# ICM40609.net
KiCad netlist of a schematic drawn in Altium Designer
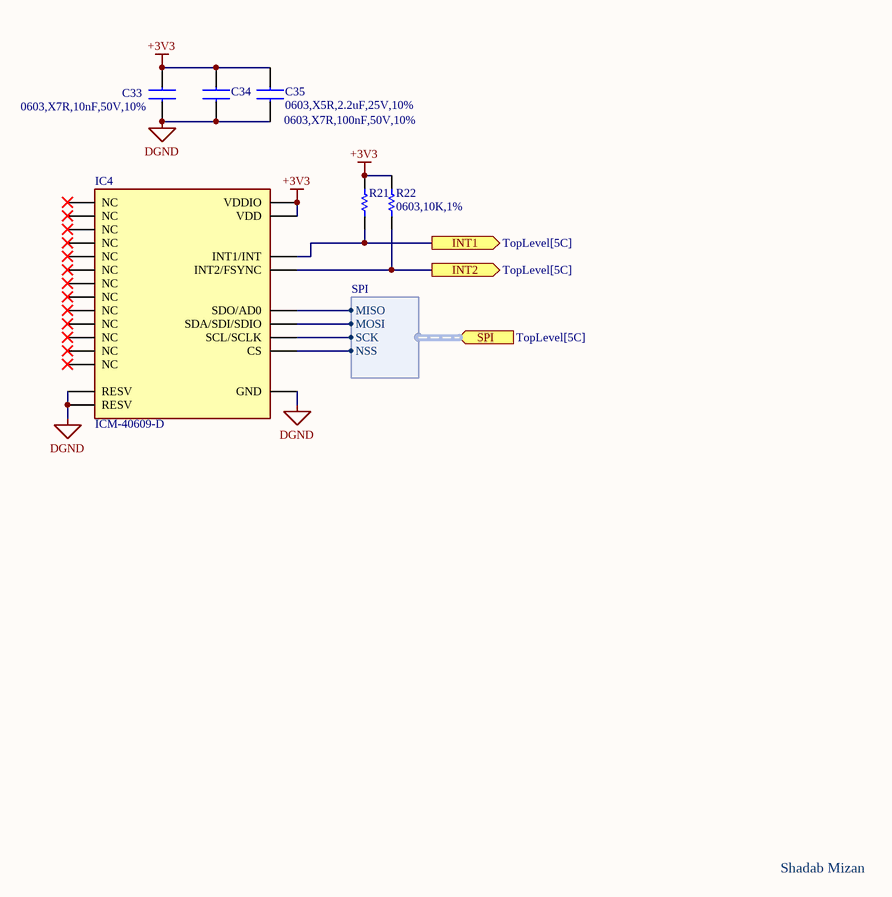
[diagram p0: ICM40609.SchDoc]

(export (version "E")
  (design (tool "Eeschema 10.0.6"))
  (components
    (comp (ref "C33")
      (value "0603,X7R,10nF,50V,10%")
      (footprint "CAPC1608X90N")
      (description "10nF ±10% 50V Ceramic Capacitor X7R 0603")
      (fields (field (name "LCSC PART #") "C57112") (field (name "MANU PART #") "0603B103K500NT"))
      (libsource (lib "flight-controller") (part "0603B103K500NT"))
    )
    (comp (ref "C34")
      (value "0603,X7R,100nF,50V,10%")
      (footprint "CAPC1608X90N")
      (description "50V 100nF X7R ±10% 0603 Multilayer Ceramic Capacitors MLCC - SMD/SMT ROHS")
      (fields (field (name "LCSC PART #") "C14663") (field (name "MANU PART #") "CC0603KRX7R9BB104"))
      (libsource (lib "flight-controller") (part "CC0603KRX7R9BB104"))
    )
    (comp (ref "C35")
      (value "0603,X5R,2.2uF,25V,10%")
      (footprint "CAPC1608X90N")
      (description "2.2 µF ±10% 25V Ceramic Capacitor X5R 0603 (1608 Metric)")
      (fields (field (name "MANU PART #") "CL10A225KO8NNNC") (field (name "LCSC PART #") "C23630"))
      (libsource (lib "flight-controller") (part "CL10A225KO8NNNC"))
    )
    (comp (ref "IC4")
      (value "ICM-40609-D")
      (footprint "LGA-24_L3.0-W3.0-P0.40-TL")
      (description "LGA24-3x3 IMUs (Inertial Measurement Units) RoHS")
      (fields (field (name "LCSC PART #") "C5360621"))
      (libsource (lib "flight-controller") (part "ICM-40609-D"))
    )
    (comp (ref "R21")
      (value "0603,10K,1%")
      (footprint "RESC1608X90N")
      (description "100mW Thick Film Resistor 75V ±100ppm/℃ ±1% 10kΩ 0603 Chip Resistor - Surface Mount ROHS")
      (fields (field (name "LCSC PART #") "C25804") (field (name "MANU PART #") "0603WAF1002T5E"))
      (libsource (lib "flight-controller") (part "0603WAF1002T5E"))
    )
    (comp (ref "R22")
      (value "0603,10K,1%")
      (footprint "RESC1608X90N")
      (description "100mW Thick Film Resistor 75V ±100ppm/℃ ±1% 10kΩ 0603 Chip Resistor - Surface Mount ROHS")
      (fields (field (name "LCSC PART #") "C25804") (field (name "MANU PART #") "0603WAF1002T5E"))
      (libsource (lib "flight-controller") (part "0603WAF1002T5E"))
    )
  )
  (nets
    (net (code "2") (name "+3V3") (class "Default")
      (node (ref "C33") (pin "2") (pinfunction "2_2") (pintype "passive"))
      (node (ref "C34") (pin "2") (pinfunction "2_2") (pintype "passive"))
      (node (ref "C35") (pin "2") (pinfunction "2_2") (pintype "passive"))
      (node (ref "IC4") (pin "13") (pinfunction "VDD_13") (pintype "passive"))
      (node (ref "IC4") (pin "8") (pinfunction "VDDIO_8") (pintype "passive"))
      (node (ref "R21") (pin "2") (pinfunction "2_2") (pintype "passive"))
      (node (ref "R22") (pin "2") (pinfunction "2_2") (pintype "passive"))
    )
    (net (code "3") (name "/INT1") (class "Default")
      (node (ref "IC4") (pin "12") (pinfunction "INT1/INT_12") (pintype "passive"))
      (node (ref "R21") (pin "1") (pinfunction "1_1") (pintype "passive"))
    )
    (net (code "4") (name "/INT2") (class "Default")
      (node (ref "IC4") (pin "19") (pinfunction "INT2/FSYNC_19") (pintype "passive"))
      (node (ref "R22") (pin "1") (pinfunction "1_1") (pintype "passive"))
    )
    (net (code "5") (name "/MISO") (class "Default")
      (node (ref "IC4") (pin "9") (pinfunction "SDO/AD0_9") (pintype "passive"))
    )
    (net (code "6") (name "/MOSI") (class "Default")
      (node (ref "IC4") (pin "24") (pinfunction "SDA/SDI/SDIO_24") (pintype "passive"))
    )
    (net (code "7") (name "/NSS") (class "Default")
      (node (ref "IC4") (pin "22") (pinfunction "CS_22") (pintype "passive"))
    )
    (net (code "8") (name "/SCK") (class "Default")
      (node (ref "IC4") (pin "23") (pinfunction "SCL/SCLK_23") (pintype "passive"))
    )
    (net (code "10") (name "DGND") (class "Default")
      (node (ref "C33") (pin "1") (pinfunction "1_1") (pintype "passive"))
      (node (ref "C34") (pin "1") (pinfunction "1_1") (pintype "passive"))
      (node (ref "C35") (pin "1") (pinfunction "1_1") (pintype "passive"))
      (node (ref "IC4") (pin "11") (pinfunction "RESV_11") (pintype "passive"))
      (node (ref "IC4") (pin "18") (pinfunction "GND_18") (pintype "passive"))
      (node (ref "IC4") (pin "20") (pinfunction "RESV_20") (pintype "passive"))
    )
    (net (code "11") (name "unconnected-(IC4-NC-Pad1)") (class "Default")
      (node (ref "IC4") (pin "1") (pinfunction "NC_1") (pintype "passive+no_connect"))
    )
    (net (code "12") (name "unconnected-(IC4-NC-Pad2)") (class "Default")
      (node (ref "IC4") (pin "2") (pinfunction "NC_2") (pintype "passive+no_connect"))
    )
    (net (code "13") (name "unconnected-(IC4-NC-Pad3)") (class "Default")
      (node (ref "IC4") (pin "3") (pinfunction "NC_3") (pintype "passive+no_connect"))
    )
    (net (code "14") (name "unconnected-(IC4-NC-Pad4)") (class "Default")
      (node (ref "IC4") (pin "4") (pinfunction "NC_4") (pintype "passive+no_connect"))
    )
    (net (code "15") (name "unconnected-(IC4-NC-Pad5)") (class "Default")
      (node (ref "IC4") (pin "5") (pinfunction "NC_5") (pintype "passive+no_connect"))
    )
    (net (code "16") (name "unconnected-(IC4-NC-Pad6)") (class "Default")
      (node (ref "IC4") (pin "6") (pinfunction "NC_6") (pintype "passive+no_connect"))
    )
    (net (code "17") (name "unconnected-(IC4-NC-Pad7)") (class "Default")
      (node (ref "IC4") (pin "7") (pinfunction "NC_7") (pintype "passive+no_connect"))
    )
    (net (code "18") (name "unconnected-(IC4-NC-Pad10)") (class "Default")
      (node (ref "IC4") (pin "10") (pinfunction "NC_10") (pintype "passive+no_connect"))
    )
    (net (code "19") (name "unconnected-(IC4-NC-Pad14)") (class "Default")
      (node (ref "IC4") (pin "14") (pinfunction "NC_14") (pintype "passive+no_connect"))
    )
    (net (code "20") (name "unconnected-(IC4-NC-Pad15)") (class "Default")
      (node (ref "IC4") (pin "15") (pinfunction "NC_15") (pintype "passive+no_connect"))
    )
    (net (code "21") (name "unconnected-(IC4-NC-Pad16)") (class "Default")
      (node (ref "IC4") (pin "16") (pinfunction "NC_16") (pintype "passive+no_connect"))
    )
    (net (code "22") (name "unconnected-(IC4-NC-Pad17)") (class "Default")
      (node (ref "IC4") (pin "17") (pinfunction "NC_17") (pintype "passive+no_connect"))
    )
    (net (code "23") (name "unconnected-(IC4-NC-Pad21)") (class "Default")
      (node (ref "IC4") (pin "21") (pinfunction "NC_21") (pintype "passive+no_connect"))
    )
  )
)
